# ModuleNguonCungCap.net
KiCad netlist of a schematic drawn in Altium Designer
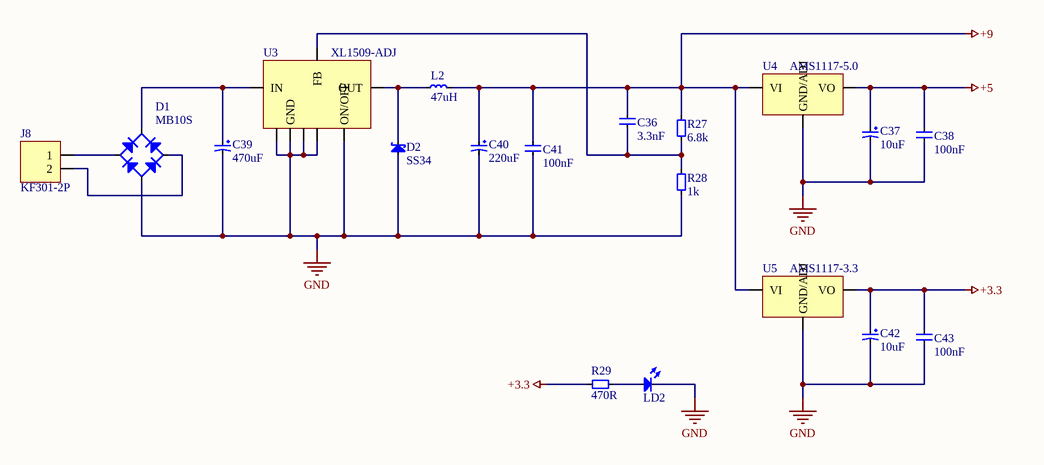
[diagram p0: ModuleNguonCungCap.SchDoc]

(export (version "E")
  (design (tool "Eeschema 10.0.6"))
  (components
    (comp (ref "C36")
      (value "3.3nF")
      (footprint "C-0805")
      (description "Cac Loai Tu Khong Phan Cuc")
      (libsource (lib "phatvu1294_Lib") (part "CAP"))
    )
    (comp (ref "C37")
      (value "10uF")
      (footprint "C-ELE-1.5-4X7MM")
      (description "Cac Loai Tu Hoa")
      (libsource (lib "phatvu1294_Lib") (part "CAP-ELE"))
    )
    (comp (ref "C38")
      (value "100nF")
      (footprint "C-0805")
      (description "Cac Loai Tu Khong Phan Cuc")
      (libsource (lib "phatvu1294_Lib") (part "CAP"))
    )
    (comp (ref "C39")
      (value "470uF")
      (footprint "C-ELE-2.5-6.3X11MM")
      (description "Cac Loai Tu Hoa")
      (libsource (lib "phatvu1294_Lib") (part "CAP-ELE"))
    )
    (comp (ref "C40")
      (value "220uF")
      (footprint "C-ELE-2.5-6.3X11MM")
      (description "Cac Loai Tu Hoa")
      (libsource (lib "phatvu1294_Lib") (part "CAP-ELE"))
    )
    (comp (ref "C41")
      (value "100nF")
      (footprint "C-0805")
      (description "Cac Loai Tu Khong Phan Cuc")
      (libsource (lib "phatvu1294_Lib") (part "CAP"))
    )
    (comp (ref "C42")
      (value "10uF")
      (footprint "C-ELE-1.5-4X7MM")
      (description "Cac Loai Tu Hoa")
      (libsource (lib "phatvu1294_Lib") (part "CAP-ELE"))
    )
    (comp (ref "C43")
      (value "100nF")
      (footprint "C-0805")
      (description "Cac Loai Tu Khong Phan Cuc")
      (libsource (lib "phatvu1294_Lib") (part "CAP"))
    )
    (comp (ref "D1")
      (value "MB10S")
      (footprint "BRIDGE-MBS")
      (description "Cac Loai Diode Cau")
      (libsource (lib "Discrete") (part "BRIDGE"))
    )
    (comp (ref "D2")
      (value "SS34")
      (footprint "DO-214AC-SMA")
      (description "Diode Schottky 1N5822 3A 40V Dan")
      (libsource (lib "Discrete") (part "SS34"))
    )
    (comp (ref "J8")
      (value "KF301-2P")
      (footprint "KF301-2P-5.0")
      (description "Dau Ket Noi KF301 2 Chan")
      (libsource (lib "phatvu1294_Lib") (part "KF301-2P"))
    )
    (comp (ref "L2")
      (value "47uH")
      (footprint "L-PK0608-2.5-7X10MM")
      (description "Cac Loai Cuon Cam Don")
      (libsource (lib "phatvu1294_Lib") (part "IND"))
    )
    (comp (ref "LD2")
      (value "PWR")
      (footprint "LED-0805-RED")
      (description "Cac Loai LED Don")
      (libsource (lib "phatvu1294_Lib") (part "LED"))
    )
    (comp (ref "R27")
      (value "6.8k")
      (footprint "R-0805")
      (description "Cac Loai Dien Tro")
      (libsource (lib "phatvu1294_Lib") (part "RES"))
    )
    (comp (ref "R28")
      (value "1k")
      (footprint "R-0805")
      (description "Cac Loai Dien Tro")
      (libsource (lib "phatvu1294_Lib") (part "RES"))
    )
    (comp (ref "R29")
      (value "470R")
      (footprint "R-0805")
      (description "Cac Loai Dien Tro")
      (libsource (lib "phatvu1294_Lib") (part "RES"))
    )
    (comp (ref "U3")
      (value "XL1509-ADJ")
      (footprint "SO8-1.27-150MIL")
      (description "IC On Ap Chuyen Mach 2A")
      (libsource (lib "phatvu1294_Lib") (part "XL1509"))
    )
    (comp (ref "U4")
      (value "AMS1117-5.0")
      (footprint "SOT223")
      (description "IC On Ap Tuyen Tinh AMS1117 1A")
      (libsource (lib "phatvu1294_Lib") (part "AMS1117"))
    )
    (comp (ref "U5")
      (value "AMS1117-3.3")
      (footprint "SOT223")
      (description "IC On Ap Tuyen Tinh AMS1117 1A")
      (libsource (lib "phatvu1294_Lib") (part "AMS1117"))
    )
  )
  (nets
    (net (code "1") (name "+3.3") (class "Default")
      (node (ref "C42") (pin "1") (pinfunction "1_1") (pintype "passive"))
      (node (ref "C43") (pin "2") (pinfunction "2_2") (pintype "passive"))
      (node (ref "R29") (pin "1") (pinfunction "1_1") (pintype "passive"))
      (node (ref "U5") (pin "2") (pinfunction "VO_2") (pintype "power_in"))
    )
    (net (code "2") (name "+5") (class "Default")
      (node (ref "C37") (pin "1") (pinfunction "1_1") (pintype "passive"))
      (node (ref "C38") (pin "2") (pinfunction "2_2") (pintype "passive"))
      (node (ref "U4") (pin "2") (pinfunction "VO_2") (pintype "power_in"))
    )
    (net (code "3") (name "+9") (class "Default")
      (node (ref "C36") (pin "2") (pinfunction "2_2") (pintype "passive"))
      (node (ref "C40") (pin "1") (pinfunction "1_1") (pintype "passive"))
      (node (ref "C41") (pin "2") (pinfunction "2_2") (pintype "passive"))
      (node (ref "L2") (pin "2") (pinfunction "2_2") (pintype "passive"))
      (node (ref "R27") (pin "2") (pinfunction "2_2") (pintype "passive"))
      (node (ref "U4") (pin "3") (pinfunction "VI_3") (pintype "power_in"))
      (node (ref "U5") (pin "3") (pinfunction "VI_3") (pintype "power_in"))
    )
    (net (code "4") (name "GND") (class "Default")
      (node (ref "C37") (pin "2") (pinfunction "2_2") (pintype "passive"))
      (node (ref "C38") (pin "1") (pinfunction "1_1") (pintype "passive"))
      (node (ref "C39") (pin "2") (pinfunction "2_2") (pintype "passive"))
      (node (ref "C40") (pin "2") (pinfunction "2_2") (pintype "passive"))
      (node (ref "C41") (pin "1") (pinfunction "1_1") (pintype "passive"))
      (node (ref "C42") (pin "2") (pinfunction "2_2") (pintype "passive"))
      (node (ref "C43") (pin "1") (pinfunction "1_1") (pintype "passive"))
      (node (ref "D1") (pin "DC-") (pinfunction "DC-_DC-") (pintype "passive"))
      (node (ref "D2") (pin "1") (pinfunction "1_1") (pintype "passive"))
      (node (ref "LD2") (pin "2") (pinfunction "2_2") (pintype "passive"))
      (node (ref "R28") (pin "1") (pinfunction "1_1") (pintype "passive"))
      (node (ref "U3") (pin "4") (pinfunction "ON/OFF_4") (pintype "passive"))
      (node (ref "U3") (pin "5") (pinfunction "GND_5") (pintype "passive"))
      (node (ref "U3") (pin "6") (pinfunction "GND_6") (pintype "passive"))
      (node (ref "U3") (pin "7") (pinfunction "GND_7") (pintype "passive"))
      (node (ref "U3") (pin "8") (pinfunction "GND_8") (pintype "passive"))
      (node (ref "U4") (pin "1") (pinfunction "GND/ADJ_1") (pintype "power_in"))
      (node (ref "U5") (pin "1") (pinfunction "GND/ADJ_1") (pintype "power_in"))
    )
    (net (code "5") (name "Net-(D1-PadAC1)") (class "Default")
      (node (ref "D1") (pin "AC1") (pinfunction "AC1_AC1") (pintype "passive"))
      (node (ref "J8") (pin "1") (pinfunction "1_1") (pintype "passive"))
    )
    (net (code "6") (name "Net-(D1-PadAC2)") (class "Default")
      (node (ref "D1") (pin "AC2") (pinfunction "AC2_AC2") (pintype "passive"))
      (node (ref "J8") (pin "2") (pinfunction "2_2") (pintype "passive"))
    )
    (net (code "7") (name "Net-(LD2-Pad1)") (class "Default")
      (node (ref "LD2") (pin "1") (pinfunction "1_1") (pintype "passive"))
      (node (ref "R29") (pin "2") (pinfunction "2_2") (pintype "passive"))
    )
    (net (code "8") (name "Net-(U3-FB)") (class "Default")
      (node (ref "C36") (pin "1") (pinfunction "1_1") (pintype "passive"))
      (node (ref "R27") (pin "1") (pinfunction "1_1") (pintype "passive"))
      (node (ref "R28") (pin "2") (pinfunction "2_2") (pintype "passive"))
      (node (ref "U3") (pin "3") (pinfunction "FB_3") (pintype "passive"))
    )
    (net (code "9") (name "Net-(U3-IN)") (class "Default")
      (node (ref "C39") (pin "1") (pinfunction "1_1") (pintype "passive"))
      (node (ref "D1") (pin "DC+") (pinfunction "DC+_DC+") (pintype "passive"))
      (node (ref "U3") (pin "1") (pinfunction "IN_1") (pintype "passive"))
    )
    (net (code "10") (name "Net-(U3-OUT)") (class "Default")
      (node (ref "D2") (pin "2") (pinfunction "2_2") (pintype "passive"))
      (node (ref "L2") (pin "1") (pinfunction "1_1") (pintype "passive"))
      (node (ref "U3") (pin "2") (pinfunction "OUT_2") (pintype "passive"))
    )
  )
)
